# 4_MCU.net
KiCad netlist of a schematic drawn in Altium Designer
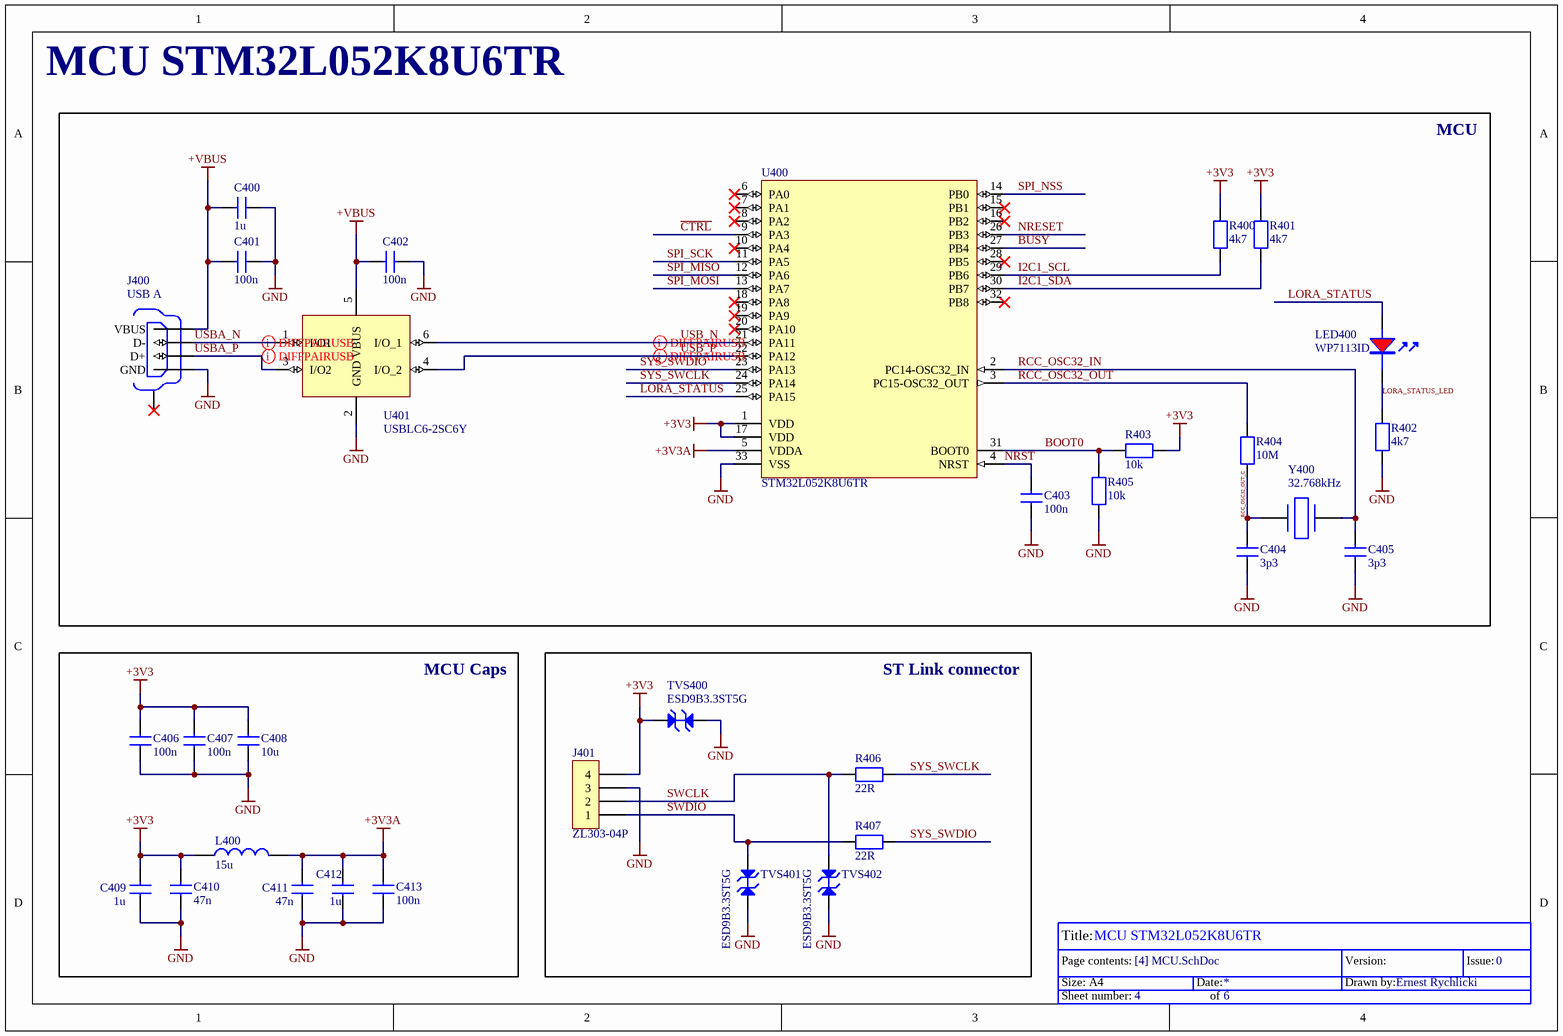
[diagram p0: [4] MCU.SchDoc]

(export (version "E")
  (design (tool "Eeschema 10.0.6"))
  (components
    (comp (ref "C400")
      (value "1u")
      (footprint "C0402")
      (description "Multilayer Ceramic Capacitor, 1 uF, 10%, X5r, 10 V, 0402 [1005 Metric]")
      (fields
        (field (name "MANUFACTURER") "Walsin Technologies")
        (field (name "MANUFACTURER PART NUMBER") "0402X105K100CT")
      )
      (libsource (lib "ER_SCH_LIB") (part "0402X105K100CT"))
    )
    (comp (ref "C401")
      (value "100n")
      (footprint "C0402")
      (description "Multilayer Ceramic Capacitor, 0.1 uF, 25 V, ± 10%, X7R, 0402 [1005 Metric]")
      (fields
        (field (name "MANUFACTURER") "Kyocera AVX")
        (field (name "MANUFACTURER PART NUMBER") "04023C104KAT2A")
      )
      (libsource (lib "ER_SCH_LIB") (part "04023C104KAT2A"))
    )
    (comp (ref "C402")
      (value "100n")
      (footprint "C0402")
      (description "Multilayer Ceramic Capacitor, 0.1 uF, 25 V, ± 10%, X7R, 0402 [1005 Metric]")
      (fields
        (field (name "MANUFACTURER") "Kyocera AVX")
        (field (name "MANUFACTURER PART NUMBER") "04023C104KAT2A")
      )
      (libsource (lib "ER_SCH_LIB") (part "04023C104KAT2A"))
    )
    (comp (ref "C403")
      (value "100n")
      (footprint "C0603")
      (description "0603 0.1 uF 25 V ±10% Tolerance X7R Automotive Multilayer Ceramic Capacitor")
      (fields
        (field (name "MANUFACTURER") "Kyocera AVX")
        (field (name "MANUFACTURER PART NUMBER") "06033C104K4T2A")
      )
      (libsource (lib "ER_SCH_LIB") (part "06033C104K4T2A"))
    )
    (comp (ref "C404")
      (value "3p3")
      (footprint "C0402")
      (description "0402 3.3 pF 50 V ±0.1 pF Tolerance C0G SMT Multilayer Ceramic Capacitor")
      (fields
        (field (name "MANUFACTURER") "Murata")
        (field (name "MANUFACTURER PART NUMBER") "GRM1555C1H3R3BA01D")
      )
      (libsource (lib "ER_SCH_LIB") (part "GRM1555C1H3R3BA01D"))
    )
    (comp (ref "C405")
      (value "3p3")
      (footprint "C0402")
      (description "0402 3.3 pF 50 V ±0.1 pF Tolerance C0G SMT Multilayer Ceramic Capacitor")
      (fields
        (field (name "MANUFACTURER") "Murata")
        (field (name "MANUFACTURER PART NUMBER") "GRM1555C1H3R3BA01D")
      )
      (libsource (lib "ER_SCH_LIB") (part "GRM1555C1H3R3BA01D"))
    )
    (comp (ref "C406")
      (value "100n")
      (footprint "C0402")
      (description "Multilayer Ceramic Capacitor, 0.1 uF, 25 V, ± 10%, X7R, 0402 [1005 Metric]")
      (fields
        (field (name "MANUFACTURER") "Kyocera AVX")
        (field (name "MANUFACTURER PART NUMBER") "04023C104KAT2A")
      )
      (libsource (lib "ER_SCH_LIB") (part "04023C104KAT2A"))
    )
    (comp (ref "C407")
      (value "100n")
      (footprint "C0402")
      (description "Multilayer Ceramic Capacitor, 0.1 uF, 25 V, ± 10%, X7R, 0402 [1005 Metric]")
      (fields
        (field (name "MANUFACTURER") "Kyocera AVX")
        (field (name "MANUFACTURER PART NUMBER") "04023C104KAT2A")
      )
      (libsource (lib "ER_SCH_LIB") (part "04023C104KAT2A"))
    )
    (comp (ref "C408")
      (value "10u")
      (footprint "C0402")
      (description "Capacitor Ceramic Mlcc 0402 10UF 6.3V SMD")
      (fields
        (field (name "MANUFACTURER") "Murata")
        (field (name "MANUFACTURER PART NUMBER") "GRJ155R60J106ME11D")
      )
      (libsource (lib "ER_SCH_LIB") (part "GRJ155R60J106ME11D"))
    )
    (comp (ref "C409")
      (value "1u")
      (footprint "C0402")
      (description "Multilayer Ceramic Capacitor, 1 uF, 10%, X5r, 10 V, 0402 [1005 Metric]")
      (fields
        (field (name "MANUFACTURER") "Walsin Technologies")
        (field (name "MANUFACTURER PART NUMBER") "0402X105K100CT")
      )
      (libsource (lib "ER_SCH_LIB") (part "0402X105K100CT"))
    )
    (comp (ref "C410")
      (value "47n")
      (footprint "C0402")
      (description "Cap Ceramic 0.047uF 16V X7R 10% SMD 0402 125°C Paper T/R")
      (fields
        (field (name "MANUFACTURER") "Murata")
        (field (name "MANUFACTURER PART NUMBER") "GRM155R71C473KA01J")
      )
      (libsource (lib "ER_SCH_LIB") (part "GRM155R71C473KA01J"))
    )
    (comp (ref "C411")
      (value "47n")
      (footprint "C0402")
      (description "Cap Ceramic 0.047uF 16V X7R 10% SMD 0402 125°C Paper T/R")
      (fields
        (field (name "MANUFACTURER") "Murata")
        (field (name "MANUFACTURER PART NUMBER") "GRM155R71C473KA01J")
      )
      (libsource (lib "ER_SCH_LIB") (part "GRM155R71C473KA01J"))
    )
    (comp (ref "C412")
      (value "1u")
      (footprint "C0402")
      (description "Multilayer Ceramic Capacitor, 1 uF, 10%, X5r, 10 V, 0402 [1005 Metric]")
      (fields
        (field (name "MANUFACTURER") "Walsin Technologies")
        (field (name "MANUFACTURER PART NUMBER") "0402X105K100CT")
      )
      (libsource (lib "ER_SCH_LIB") (part "0402X105K100CT"))
    )
    (comp (ref "C413")
      (value "100n")
      (footprint "C0402")
      (description "Multilayer Ceramic Capacitor, 0.1 uF, 25 V, ± 10%, X7R, 0402 [1005 Metric]")
      (fields
        (field (name "MANUFACTURER") "Kyocera AVX")
        (field (name "MANUFACTURER PART NUMBER") "04023C104KAT2A")
      )
      (libsource (lib "ER_SCH_LIB") (part "04023C104KAT2A"))
    )
    (comp (ref "J400")
      (value "USB A")
      (footprint "CONN_USB_RT_ANG")
      (description "CONN USB RT ANG RECPT TYPE A BLK")
      (fields (field (name "MANUFACTURER") "Molex") (field (name "MANUFACTURER PART NUMBER") "0676430910"))
      (libsource (lib "ER_SCH_LIB") (part "0676430910"))
    )
    (comp (ref "J401")
      (value "ZL303-04P")
      (footprint "HEADER1X4 _2mm")
      (description "Pin Header, 4-Pin, 2mm")
      (libsource (lib "ER_SCH_LIB") (part "ZL303-04P"))
    )
    (comp (ref "L400")
      (value "15u")
      (footprint "L0805")
      (description "Inductor Power Shielded Multi-Layer 15uH 20% 2MHz Ferrite 0.25A 1.235Ohm DCR 0805 T/R")
      (fields
        (field (name "MANUFACTURER") "TDK")
        (field (name "MANUFACTURER PART NUMBER") "MLZ2012M150WT000")
      )
      (libsource (lib "ER_SCH_LIB") (part "MLZ2012M150WT000"))
    )
    (comp (ref "LED400")
      (value "WP7113ID")
      (footprint "LED5mm")
      (description "Red T-1 3/4 5 mm 30° 50 mcd 2.2 V Tinted Solid State LED Lamp Through Hole")
      (fields (field (name "MANUFACTURER") "Kingbright"))
      (libsource (lib "ER_SCH_LIB") (part "WP7113ID"))
    )
    (comp (ref "R400")
      (value "4k7")
      (footprint "R0603")
      (description "Res Thick Film 0603 4.7K Ohm 1% 1/10W ±100ppm/°C Molded SMD Paper T/R")
      (fields
        (field (name "MANUFACTURER") "Yageo")
        (field (name "MANUFACTURER PART NUMBER") "AF0603FR-074K7L")
      )
      (libsource (lib "ER_SCH_LIB") (part "AF0603FR-074K7L"))
    )
    (comp (ref "R401")
      (value "4k7")
      (footprint "R0603")
      (description "Res Thick Film 0603 4.7K Ohm 1% 1/10W ±100ppm/°C Molded SMD Paper T/R")
      (fields
        (field (name "MANUFACTURER") "Yageo")
        (field (name "MANUFACTURER PART NUMBER") "AF0603FR-074K7L")
      )
      (libsource (lib "ER_SCH_LIB") (part "AF0603FR-074K7L"))
    )
    (comp (ref "R402")
      (value "4k7")
      (footprint "R0603")
      (description "Res Thick Film 0603 4.7K Ohm 1% 1/10W ±100ppm/°C Molded SMD Paper T/R")
      (fields
        (field (name "MANUFACTURER") "Yageo")
        (field (name "MANUFACTURER PART NUMBER") "AF0603FR-074K7L")
      )
      (libsource (lib "ER_SCH_LIB") (part "AF0603FR-074K7L"))
    )
    (comp (ref "R403")
      (value "10k")
      (footprint "R0603")
      (description "SMD Chip Resistor, 10 kOhm, ± 5%, 100 mW, 0603 [1608 Metric], Thick Film, General Purpose")
      (fields
        (field (name "MANUFACTURER") "Yageo")
        (field (name "MANUFACTURER PART NUMBER") "AC0603JR-0710KL")
      )
      (libsource (lib "ER_SCH_LIB") (part "AC0603JR-0710KL"))
    )
    (comp (ref "R404")
      (value "10M")
      (footprint "R0603")
      (description "SMD Chip Resistor, 10 MOhm, ± 1%, 100 mW, 0603 [1608 Metric], Thick Film, General Purpose")
      (fields
        (field (name "MANUFACTURER") "Yageo")
        (field (name "MANUFACTURER PART NUMBER") "RC0603FR-0710ML")
      )
      (libsource (lib "ER_SCH_LIB") (part "RC0603FR-0710ML"))
    )
    (comp (ref "R405")
      (value "10k")
      (footprint "R0603")
      (description "SMD Chip Resistor, 10 kOhm, ± 5%, 100 mW, 0603 [1608 Metric], Thick Film, General Purpose")
      (fields
        (field (name "MANUFACTURER") "Yageo")
        (field (name "MANUFACTURER PART NUMBER") "AC0603JR-0710KL")
      )
      (libsource (lib "ER_SCH_LIB") (part "AC0603JR-0710KL"))
    )
    (comp (ref "R406")
      (value "22R")
      (footprint "R0603")
      (description "SMD Chip Resistor, 22 Ohm, ± 5%, 100 mW, 0603 [1608 Metric], Thick Film, General Purpose")
      (fields
        (field (name "MANUFACTURER") "Yageo")
        (field (name "MANUFACTURER PART NUMBER") "RC0603JR-0722RL")
      )
      (libsource (lib "ER_SCH_LIB") (part "RC0603JR-0722RL"))
    )
    (comp (ref "R407")
      (value "22R")
      (footprint "R0603")
      (description "SMD Chip Resistor, 22 Ohm, ± 5%, 100 mW, 0603 [1608 Metric], Thick Film, General Purpose")
      (fields
        (field (name "MANUFACTURER") "Yageo")
        (field (name "MANUFACTURER PART NUMBER") "RC0603JR-0722RL")
      )
      (libsource (lib "ER_SCH_LIB") (part "RC0603JR-0722RL"))
    )
    (comp (ref "TVS400")
      (value "ESD9B3.3ST5G")
      (footprint "SOD-923")
      (description "11.5V 2A 3.3V (Max) 5V Bidirectional SOD-923 ESD Protection Devices ROHS")
      (fields (field (name "MANUFACTURER") "ON Semiconductor"))
      (libsource (lib "ER_SCH_LIB") (part "ESD9B3.3ST5G"))
    )
    (comp (ref "TVS401")
      (value "ESD9B3.3ST5G")
      (footprint "SOD-923")
      (description "11.5V 2A 3.3V (Max) 5V Bidirectional SOD-923 ESD Protection Devices ROHS")
      (fields (field (name "MANUFACTURER") "ON Semiconductor"))
      (libsource (lib "ER_SCH_LIB") (part "ESD9B3.3ST5G"))
    )
    (comp (ref "TVS402")
      (value "ESD9B3.3ST5G")
      (footprint "SOD-923")
      (description "11.5V 2A 3.3V (Max) 5V Bidirectional SOD-923 ESD Protection Devices ROHS")
      (fields (field (name "MANUFACTURER") "ON Semiconductor"))
      (libsource (lib "ER_SCH_LIB") (part "ESD9B3.3ST5G"))
    )
    (comp (ref "U400")
      (value "STM32L052K8U6TR")
      (footprint "UFQFPN32")
      (description "Ultra-low power ARM Cortex-M0+ MCU with 64-Kbyte Flash, 32 MHz CPU, USB")
      (fields (field (name "MANUFACTURER") "STMicroelectronics"))
      (libsource (lib "ER_SCH_LIB") (part "STM32L052K8U6TR"))
    )
    (comp (ref "U401")
      (value "USBLC6-2SC6Y")
      (footprint "SOT23-6L")
      (description "USBLC6 Series 2 Line 6 V Uni / Bi Directional ESD Protection - SOT-23-6")
      (fields (field (name "MANUFACTURER") "STMicroelectronics"))
      (libsource (lib "ER_SCH_LIB") (part "USBLC6-2SC6Y"))
    )
    (comp (ref "Y400")
      (value "32.768kHz")
      (footprint "OSCILATOR_2X1_2")
      (description "Tuning Fork Crystal SMD 32.768kHz 1.2x2.0mm")
      (fields
        (field (name "MANUFACTURER") "Micro Crystal")
        (field (name "MANUFACTURER PART NUMBER") "CM8V-T1A 32.768kHz 7pF +/-20ppm TA QC")
      )
      (libsource (lib "ER_SCH_LIB") (part "CM8V-T1A 32.768kHz 7pF +/-20ppm TA QC"))
    )
  )
  (nets
    (net (code "1") (name "+3V3") (class "Default")
      (node (ref "C406") (pin "2") (pinfunction "2_2") (pintype "passive"))
      (node (ref "C407") (pin "2") (pinfunction "2_2") (pintype "passive"))
      (node (ref "C408") (pin "2") (pinfunction "2_2") (pintype "passive"))
      (node (ref "C409") (pin "2") (pinfunction "2_2") (pintype "passive"))
      (node (ref "C410") (pin "2") (pinfunction "2_2") (pintype "passive"))
      (node (ref "J401") (pin "4") (pinfunction "4_4") (pintype "passive"))
      (node (ref "L400") (pin "1") (pinfunction "1_1") (pintype "passive"))
      (node (ref "R400") (pin "2") (pinfunction "2_2") (pintype "passive"))
      (node (ref "R401") (pin "2") (pinfunction "2_2") (pintype "passive"))
      (node (ref "R403") (pin "1") (pinfunction "1_1") (pintype "passive"))
      (node (ref "TVS400") (pin "1") (pinfunction "1_1") (pintype "passive"))
      (node (ref "U400") (pin "1") (pinfunction "VDD_1") (pintype "power_in"))
      (node (ref "U400") (pin "17") (pinfunction "VDD_17") (pintype "power_in"))
    )
    (net (code "2") (name "+3V3A") (class "Default")
      (node (ref "C411") (pin "2") (pinfunction "2_2") (pintype "passive"))
      (node (ref "C412") (pin "2") (pinfunction "2_2") (pintype "passive"))
      (node (ref "C413") (pin "2") (pinfunction "2_2") (pintype "passive"))
      (node (ref "L400") (pin "2") (pinfunction "2_2") (pintype "passive"))
      (node (ref "U400") (pin "5") (pinfunction "VDDA_5") (pintype "power_in"))
    )
    (net (code "3") (name "+VBUS") (class "Default")
      (node (ref "C400") (pin "2") (pinfunction "2_2") (pintype "passive"))
      (node (ref "C401") (pin "2") (pinfunction "2_2") (pintype "passive"))
      (node (ref "C402") (pin "2") (pinfunction "2_2") (pintype "passive"))
      (node (ref "J400") (pin "1") (pinfunction "VBUS_1") (pintype "power_in"))
      (node (ref "U401") (pin "5") (pinfunction "VBUS_5") (pintype "power_in"))
    )
    (net (code "4") (name "/BOOT0") (class "Default")
      (node (ref "R403") (pin "2") (pinfunction "2_2") (pintype "passive"))
      (node (ref "R405") (pin "2") (pinfunction "2_2") (pintype "passive"))
      (node (ref "U400") (pin "31") (pinfunction "BOOT0_31") (pintype "passive"))
    )
    (net (code "5") (name "/BUSY") (class "Default")
      (node (ref "U400") (pin "27") (pinfunction "PB4_27") (pintype "bidirectional"))
    )
    (net (code "6") (name "/I2C1_SCL") (class "Default")
      (node (ref "R400") (pin "1") (pinfunction "1_1") (pintype "passive"))
      (node (ref "U400") (pin "29") (pinfunction "PB6_29") (pintype "bidirectional"))
    )
    (net (code "7") (name "/I2C1_SDA") (class "Default")
      (node (ref "R401") (pin "1") (pinfunction "1_1") (pintype "passive"))
      (node (ref "U400") (pin "30") (pinfunction "PB7_30") (pintype "bidirectional"))
    )
    (net (code "8") (name "/LORA_STATUS") (class "Default")
      (node (ref "LED400") (pin "A") (pinfunction "A_A") (pintype "passive"))
      (node (ref "U400") (pin "25") (pinfunction "PA15_25") (pintype "bidirectional"))
    )
    (net (code "9") (name "/LORA_STATUS_LED") (class "Default")
      (node (ref "LED400") (pin "K") (pinfunction "K_K") (pintype "passive"))
      (node (ref "R402") (pin "1") (pinfunction "1_1") (pintype "passive"))
    )
    (net (code "10") (name "/NRESET") (class "Default")
      (node (ref "U400") (pin "26") (pinfunction "PB3_26") (pintype "bidirectional"))
    )
    (net (code "11") (name "/NRST") (class "Default")
      (node (ref "C403") (pin "2") (pinfunction "2_2") (pintype "passive"))
      (node (ref "U400") (pin "4") (pinfunction "NRST_4") (pintype "input"))
    )
    (net (code "12") (name "/RCC_OSC32_IN") (class "Default")
      (node (ref "C405") (pin "1") (pinfunction "1_1") (pintype "passive"))
      (node (ref "U400") (pin "2") (pinfunction "PC14-OSC32_IN_2") (pintype "input"))
      (node (ref "Y400") (pin "2") (pinfunction "2_2") (pintype "power_in"))
    )
    (net (code "13") (name "/RCC_OSC32_OUT") (class "Default")
      (node (ref "R404") (pin "2") (pinfunction "2_2") (pintype "passive"))
      (node (ref "U400") (pin "3") (pinfunction "PC15-OSC32_OUT_3") (pintype "output"))
    )
    (net (code "14") (name "/RCC_OSC32_OUT_C") (class "Default")
      (node (ref "C404") (pin "1") (pinfunction "1_1") (pintype "passive"))
      (node (ref "R404") (pin "1") (pinfunction "1_1") (pintype "passive"))
      (node (ref "Y400") (pin "1") (pinfunction "1_1") (pintype "power_in"))
    )
    (net (code "15") (name "/SPI_MISO") (class "Default")
      (node (ref "U400") (pin "12") (pinfunction "PA6_12") (pintype "bidirectional"))
    )
    (net (code "16") (name "/SPI_MOSI") (class "Default")
      (node (ref "U400") (pin "13") (pinfunction "PA7_13") (pintype "bidirectional"))
    )
    (net (code "17") (name "/SPI_NSS") (class "Default")
      (node (ref "U400") (pin "14") (pinfunction "PB0_14") (pintype "bidirectional"))
    )
    (net (code "18") (name "/SPI_SCK") (class "Default")
      (node (ref "U400") (pin "11") (pinfunction "PA5_11") (pintype "bidirectional"))
    )
    (net (code "19") (name "/SWCLK") (class "Default")
      (node (ref "J401") (pin "2") (pinfunction "2_2") (pintype "passive"))
      (node (ref "R406") (pin "1") (pinfunction "1_1") (pintype "passive"))
      (node (ref "TVS402") (pin "1") (pinfunction "1_1") (pintype "passive"))
    )
    (net (code "20") (name "/SWDIO") (class "Default")
      (node (ref "J401") (pin "1") (pinfunction "1_1") (pintype "passive"))
      (node (ref "R407") (pin "1") (pinfunction "1_1") (pintype "passive"))
      (node (ref "TVS401") (pin "1") (pinfunction "1_1") (pintype "passive"))
    )
    (net (code "21") (name "/SYS_SWCLK") (class "Default")
      (node (ref "R406") (pin "2") (pinfunction "2_2") (pintype "passive"))
      (node (ref "U400") (pin "24") (pinfunction "PA14_24") (pintype "bidirectional"))
    )
    (net (code "22") (name "/SYS_SWDIO") (class "Default")
      (node (ref "R407") (pin "2") (pinfunction "2_2") (pintype "passive"))
      (node (ref "U400") (pin "23") (pinfunction "PA13_23") (pintype "bidirectional"))
    )
    (net (code "23") (name "/USBA_N") (class "Default")
      (node (ref "J400") (pin "2") (pinfunction "D-_2") (pintype "bidirectional"))
      (node (ref "U401") (pin "1") (pinfunction "I/O1_1") (pintype "bidirectional"))
    )
    (net (code "24") (name "/USBA_P") (class "Default")
      (node (ref "J400") (pin "3") (pinfunction "D+_3") (pintype "bidirectional"))
      (node (ref "U401") (pin "3") (pinfunction "I/O2_3") (pintype "bidirectional"))
    )
    (net (code "25") (name "/USB_N") (class "Default")
      (node (ref "U400") (pin "21") (pinfunction "PA11_21") (pintype "bidirectional"))
      (node (ref "U401") (pin "6") (pinfunction "I/O_1_6") (pintype "bidirectional"))
    )
    (net (code "26") (name "/USB_P") (class "Default")
      (node (ref "U400") (pin "22") (pinfunction "PA12_22") (pintype "bidirectional"))
      (node (ref "U401") (pin "4") (pinfunction "I/O_2_4") (pintype "bidirectional"))
    )
    (net (code "27") (name "/~{CTRL}") (class "Default")
      (node (ref "U400") (pin "9") (pinfunction "PA3_9") (pintype "bidirectional"))
    )
    (net (code "28") (name "GND") (class "Default")
      (node (ref "C400") (pin "1") (pinfunction "1_1") (pintype "passive"))
      (node (ref "C401") (pin "1") (pinfunction "1_1") (pintype "passive"))
      (node (ref "C402") (pin "1") (pinfunction "1_1") (pintype "passive"))
      (node (ref "C403") (pin "1") (pinfunction "1_1") (pintype "passive"))
      (node (ref "C404") (pin "2") (pinfunction "2_2") (pintype "passive"))
      (node (ref "C405") (pin "2") (pinfunction "2_2") (pintype "passive"))
      (node (ref "C406") (pin "1") (pinfunction "1_1") (pintype "passive"))
      (node (ref "C407") (pin "1") (pinfunction "1_1") (pintype "passive"))
      (node (ref "C408") (pin "1") (pinfunction "1_1") (pintype "passive"))
      (node (ref "C409") (pin "1") (pinfunction "1_1") (pintype "passive"))
      (node (ref "C410") (pin "1") (pinfunction "1_1") (pintype "passive"))
      (node (ref "C411") (pin "1") (pinfunction "1_1") (pintype "passive"))
      (node (ref "C412") (pin "1") (pinfunction "1_1") (pintype "passive"))
      (node (ref "C413") (pin "1") (pinfunction "1_1") (pintype "passive"))
      (node (ref "J400") (pin "4") (pinfunction "GND_4") (pintype "power_in"))
      (node (ref "J401") (pin "3") (pinfunction "3_3") (pintype "passive"))
      (node (ref "R402") (pin "2") (pinfunction "2_2") (pintype "passive"))
      (node (ref "R405") (pin "1") (pinfunction "1_1") (pintype "passive"))
      (node (ref "TVS400") (pin "2") (pinfunction "2_2") (pintype "passive"))
      (node (ref "TVS401") (pin "2") (pinfunction "2_2") (pintype "passive"))
      (node (ref "TVS402") (pin "2") (pinfunction "2_2") (pintype "passive"))
      (node (ref "U400") (pin "33") (pinfunction "VSS_33") (pintype "power_in"))
      (node (ref "U401") (pin "2") (pinfunction "GND_2") (pintype "power_in"))
    )
    (net (code "29") (name "unconnected-(J400-SHELL-Pad0)") (class "Default")
      (node (ref "J400") (pin "0") (pinfunction "SHELL_0") (pintype "power_in+no_connect"))
    )
    (net (code "30") (name "unconnected-(U400-PA0-Pad6)") (class "Default")
      (node (ref "U400") (pin "6") (pinfunction "PA0_6") (pintype "bidirectional+no_connect"))
    )
    (net (code "31") (name "unconnected-(U400-PA1-Pad7)") (class "Default")
      (node (ref "U400") (pin "7") (pinfunction "PA1_7") (pintype "bidirectional+no_connect"))
    )
    (net (code "32") (name "unconnected-(U400-PA2-Pad8)") (class "Default")
      (node (ref "U400") (pin "8") (pinfunction "PA2_8") (pintype "bidirectional+no_connect"))
    )
    (net (code "33") (name "unconnected-(U400-PA4-Pad10)") (class "Default")
      (node (ref "U400") (pin "10") (pinfunction "PA4_10") (pintype "bidirectional+no_connect"))
    )
    (net (code "34") (name "unconnected-(U400-PA8-Pad18)") (class "Default")
      (node (ref "U400") (pin "18") (pinfunction "PA8_18") (pintype "bidirectional+no_connect"))
    )
    (net (code "35") (name "unconnected-(U400-PA9-Pad19)") (class "Default")
      (node (ref "U400") (pin "19") (pinfunction "PA9_19") (pintype "bidirectional+no_connect"))
    )
    (net (code "36") (name "unconnected-(U400-PA10-Pad20)") (class "Default")
      (node (ref "U400") (pin "20") (pinfunction "PA10_20") (pintype "bidirectional+no_connect"))
    )
    (net (code "37") (name "unconnected-(U400-PB1-Pad15)") (class "Default")
      (node (ref "U400") (pin "15") (pinfunction "PB1_15") (pintype "bidirectional+no_connect"))
    )
    (net (code "38") (name "unconnected-(U400-PB2-Pad16)") (class "Default")
      (node (ref "U400") (pin "16") (pinfunction "PB2_16") (pintype "bidirectional+no_connect"))
    )
    (net (code "39") (name "unconnected-(U400-PB5-Pad28)") (class "Default")
      (node (ref "U400") (pin "28") (pinfunction "PB5_28") (pintype "bidirectional+no_connect"))
    )
    (net (code "40") (name "unconnected-(U400-PB8-Pad32)") (class "Default")
      (node (ref "U400") (pin "32") (pinfunction "PB8_32") (pintype "bidirectional+no_connect"))
    )
  )
)
